# Sheet_byLIN.net
KiCad netlist of a schematic drawn in Altium Designer
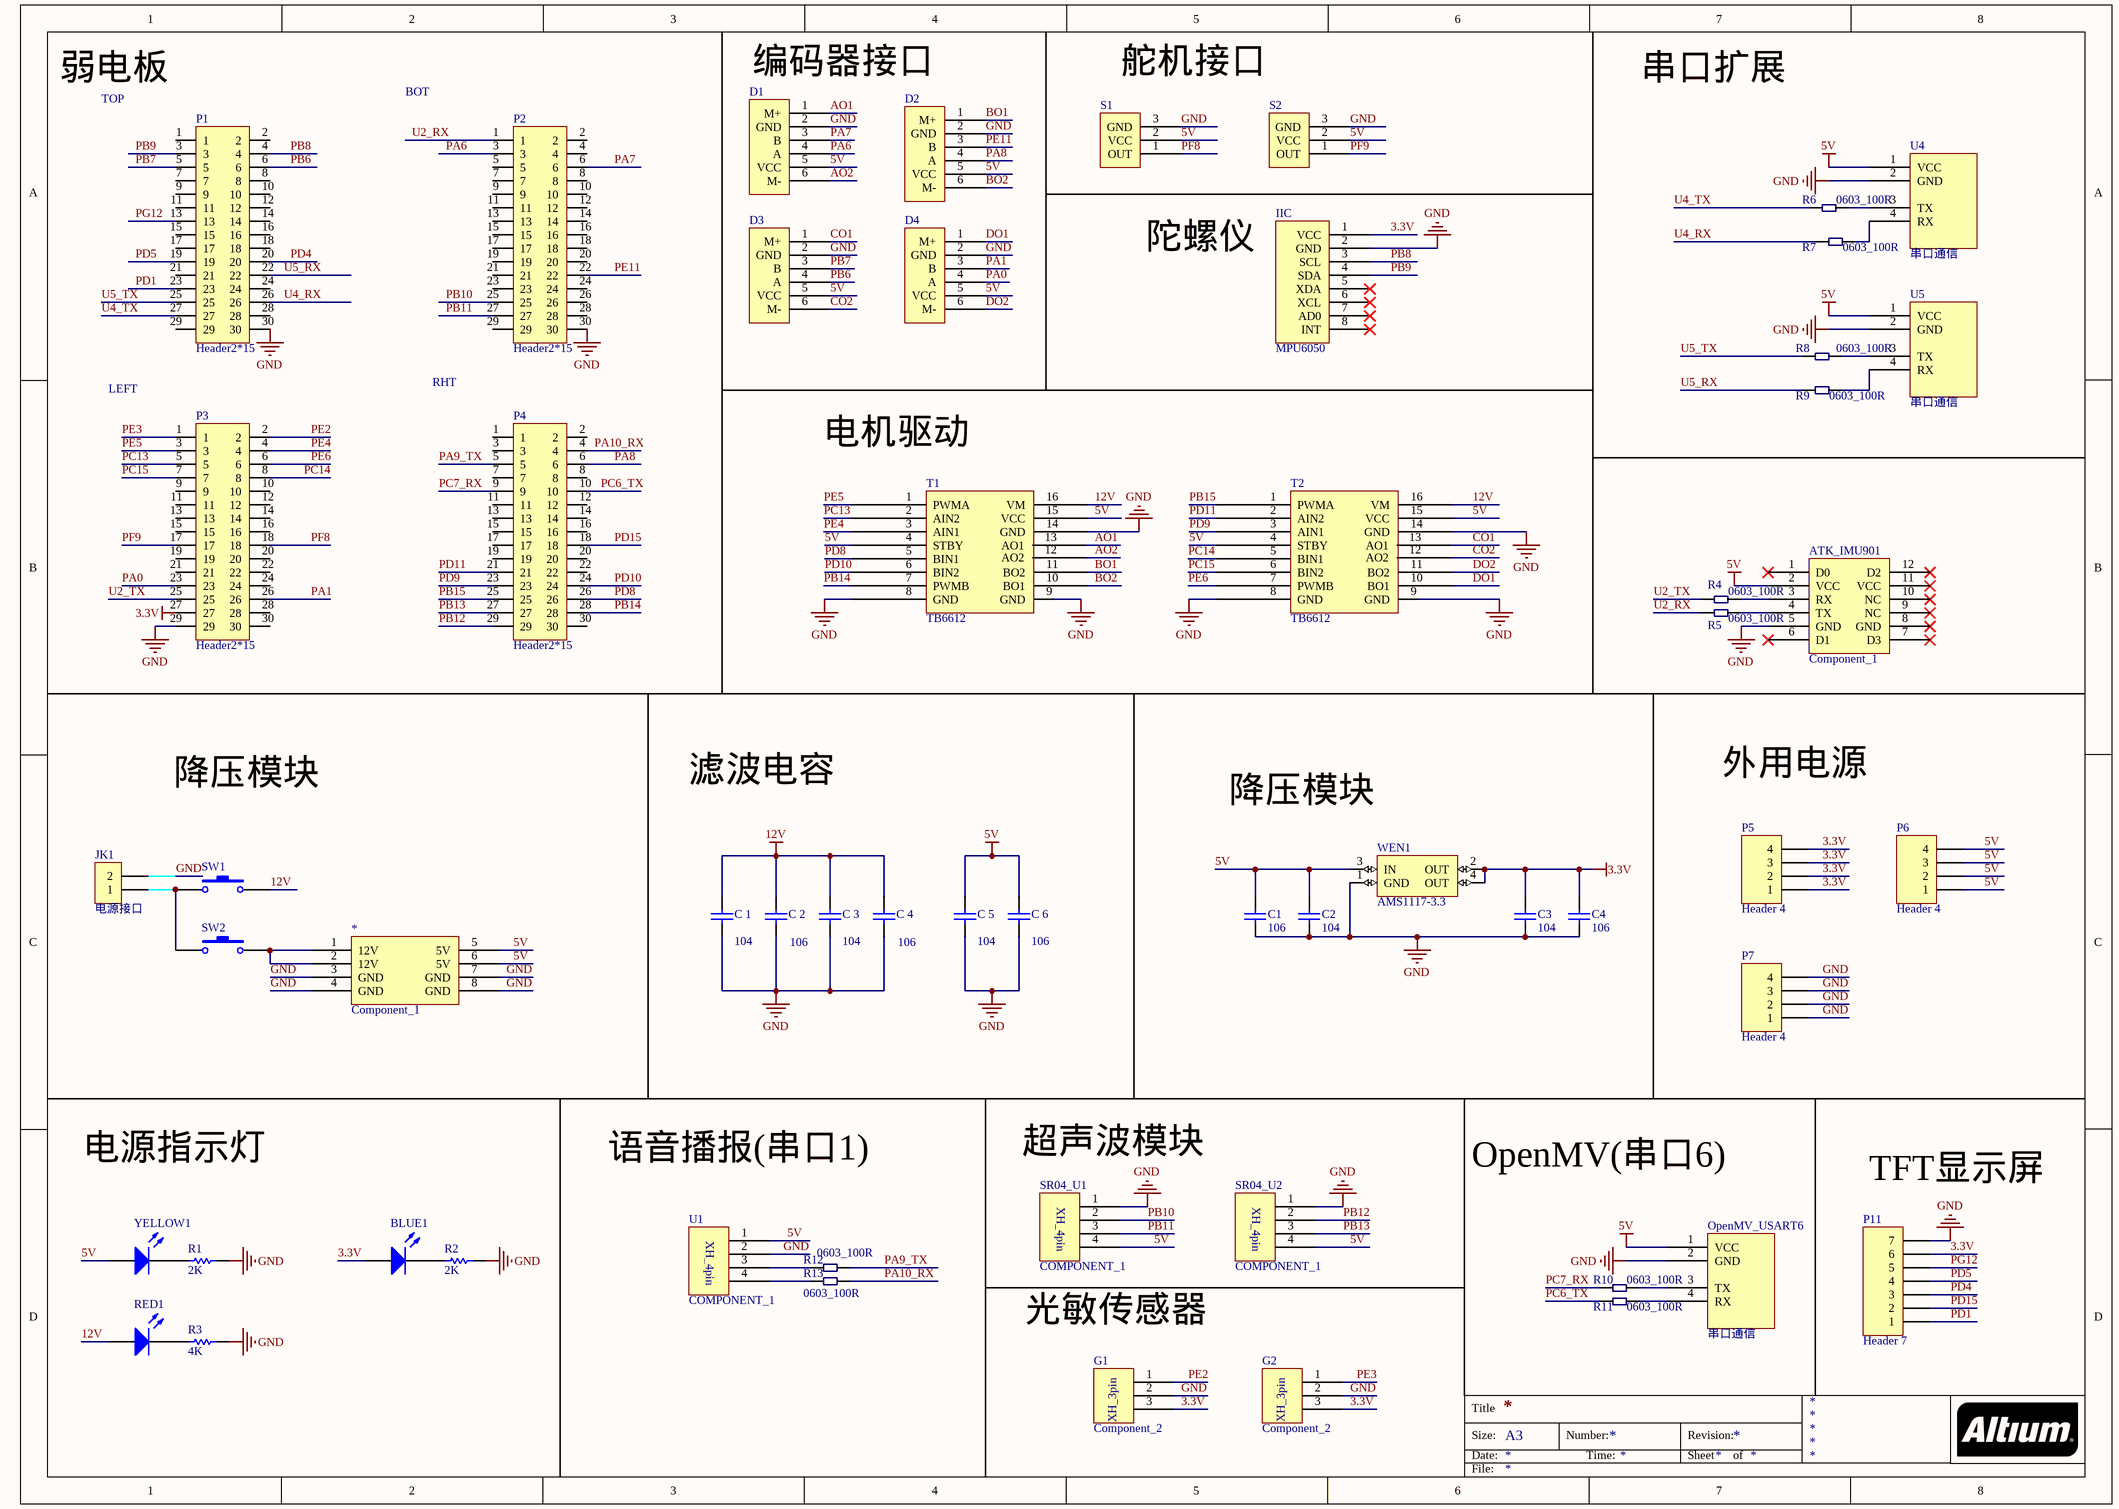
[diagram p0: Sheet_byLIN.SchDoc]

(export (version "E")
  (design (tool "Eeschema 10.0.6"))
  (components
    (comp (ref "*")
      (value "Component_1")
      (footprint "12-5V电源模块")
      (libsource (lib "稳压模块") (part "Component_1"))
    )
    (comp (ref "ATK_IMU901")
      (value "Component_1")
      (footprint "PCBComponent_1 - duplicate")
      (libsource (lib "MPU6050_v2") (part "Component_1"))
    )
    (comp (ref "BLUE1")
      (value "~")
      (footprint "LED 0805G")
      (description "Typical RED GaAs LED")
      (fields (field (name "PUBLISHER") "Altium Limited"))
      (libsource (lib "Miscellaneous Devices") (part "LED1"))
    )
    (comp (ref "C 1")
      (value "104")
      (footprint "C0805")
      (description "Capacitor")
      (fields (field (name "Comment") "Cap") (field (name "PUBLISHER") "Altium Limited"))
      (libsource (lib "Miscellaneous Devices") (part "Cap"))
    )
    (comp (ref "C 2")
      (value "106")
      (footprint "C0805")
      (description "Capacitor")
      (fields (field (name "Comment") "Cap") (field (name "PUBLISHER") "Altium Limited"))
      (libsource (lib "Miscellaneous Devices") (part "Cap"))
    )
    (comp (ref "C 3")
      (value "104")
      (footprint "C0805")
      (description "Capacitor")
      (fields (field (name "Comment") "Cap") (field (name "PUBLISHER") "Altium Limited"))
      (libsource (lib "Miscellaneous Devices") (part "Cap"))
    )
    (comp (ref "C 4")
      (value "106")
      (footprint "C0805")
      (description "Capacitor")
      (fields (field (name "Comment") "Cap") (field (name "PUBLISHER") "Altium Limited"))
      (libsource (lib "Miscellaneous Devices") (part "Cap"))
    )
    (comp (ref "C 5")
      (value "104")
      (footprint "C0805")
      (description "Capacitor")
      (fields (field (name "Comment") "Cap") (field (name "PUBLISHER") "Altium Limited"))
      (libsource (lib "Miscellaneous Devices") (part "Cap"))
    )
    (comp (ref "C 6")
      (value "106")
      (footprint "C0805")
      (description "Capacitor")
      (fields (field (name "Comment") "Cap") (field (name "PUBLISHER") "Altium Limited"))
      (libsource (lib "Miscellaneous Devices") (part "Cap"))
    )
    (comp (ref "C1")
      (value "106")
      (footprint "C 0603")
      (description "Capacitor")
      (fields (field (name "PUBLISHER") "Altium Limited"))
      (libsource (lib "Miscellaneous Devices") (part "Cap"))
    )
    (comp (ref "C2")
      (value "104")
      (footprint "C 0603")
      (description "Capacitor")
      (fields (field (name "PUBLISHER") "Altium Limited"))
      (libsource (lib "Miscellaneous Devices") (part "Cap"))
    )
    (comp (ref "C3")
      (value "104")
      (footprint "C 0603")
      (description "Capacitor")
      (fields (field (name "PUBLISHER") "Altium Limited"))
      (libsource (lib "Miscellaneous Devices") (part "Cap"))
    )
    (comp (ref "C4")
      (value "106")
      (footprint "C 0603")
      (description "Capacitor")
      (fields (field (name "PUBLISHER") "Altium Limited"))
      (libsource (lib "Miscellaneous Devices") (part "Cap"))
    )
    (comp (ref "D1") (value "~") (footprint "XH2.54-WI-6P") (libsource (lib "PCB_Project1") (part "P1")))
    (comp (ref "D2") (value "~") (footprint "XH2.54-WI-6P") (libsource (lib "PCB_Project1") (part "P1")))
    (comp (ref "D3") (value "~") (footprint "XH2.54-WI-6P") (libsource (lib "PCB_Project1") (part "P1")))
    (comp (ref "D4") (value "~") (footprint "XH2.54-WI-6P") (libsource (lib "PCB_Project1") (part "P1")))
    (comp (ref "G1")
      (value "Component_2")
      (footprint "XH2.54-LI-3P")
      (libsource (lib "XH_4PIN") (part "Component_2"))
    )
    (comp (ref "G2")
      (value "Component_2")
      (footprint "XH2.54-LI-3P")
      (libsource (lib "XH_4PIN") (part "Component_2"))
    )
    (comp (ref "IIC")
      (value "MPU6050")
      (footprint "HDR2.54-M-LI-8P")
      (libsource (lib "MPU6050") (part "MPU6050"))
    )
    (comp (ref "JK1") (value "电源接口") (footprint "XT-60") (libsource (lib "试验板") (part "VH2")))
    (comp (ref "OpenMV_USART6")
      (value "串口通信")
      (footprint "J-XH-4AW短")
      (libsource (lib "羽毛球团队") (part "XH2.54插座-4P"))
    )
    (comp (ref "P1")
      (value "Header2*15")
      (footprint "HDR2X15")
      (libsource (lib "主控V2.0核心板") (part "Header2*15"))
    )
    (comp (ref "P2")
      (value "Header2*15")
      (footprint "HDR2X15")
      (libsource (lib "主控V2.0核心板") (part "Header2*15"))
    )
    (comp (ref "P3")
      (value "Header2*15")
      (footprint "HDR2X15")
      (libsource (lib "主控V2.0核心板") (part "Header2*15"))
    )
    (comp (ref "P4")
      (value "Header2*15")
      (footprint "HDR2X15")
      (libsource (lib "主控V2.0核心板") (part "Header2*15"))
    )
    (comp (ref "P5")
      (value "Header 4")
      (footprint "HDR1X4")
      (description "Header, 4-Pin")
      (fields (field (name "PUBLISHER") "Altium Limited"))
      (libsource (lib "Miscellaneous Connectors") (part "Header 4"))
    )
    (comp (ref "P6")
      (value "Header 4")
      (footprint "HDR1X4")
      (description "Header, 4-Pin")
      (fields (field (name "PUBLISHER") "Altium Limited"))
      (libsource (lib "Miscellaneous Connectors") (part "Header 4"))
    )
    (comp (ref "P7")
      (value "Header 4")
      (footprint "HDR1X4")
      (description "Header, 4-Pin")
      (fields (field (name "PUBLISHER") "Altium Limited"))
      (libsource (lib "Miscellaneous Connectors") (part "Header 4"))
    )
    (comp (ref "P11")
      (value "Header 7")
      (footprint "HDR1X7")
      (description "Header, 7-Pin")
      (fields (field (name "PUBLISHER") "Altium Limited"))
      (libsource (lib "Miscellaneous Connectors") (part "Header 7"))
    )
    (comp (ref "R1")
      (value "2K")
      (footprint "R 0603")
      (description "Resistor")
      (fields (field (name "PUBLISHER") "Altium Limited"))
      (libsource (lib "Miscellaneous Devices") (part "Res1"))
    )
    (comp (ref "R2")
      (value "2K")
      (footprint "R 0603")
      (description "Resistor")
      (fields (field (name "PUBLISHER") "Altium Limited"))
      (libsource (lib "Miscellaneous Devices") (part "Res1"))
    )
    (comp (ref "R3")
      (value "4K")
      (footprint "R 0603")
      (description "Resistor")
      (fields (field (name "PUBLISHER") "Altium Limited"))
      (libsource (lib "Miscellaneous Devices") (part "Res1"))
    )
    (comp (ref "R4") (value "0603_100R") (footprint "0603_R") (libsource (lib "Schlib1") (part "RES")))
    (comp (ref "R5") (value "0603_100R") (footprint "0603_R") (libsource (lib "Schlib1") (part "RES")))
    (comp (ref "R6") (value "0603_100R") (footprint "0603_R") (libsource (lib "Schlib1") (part "RES")))
    (comp (ref "R7") (value "0603_100R") (footprint "0603_R") (libsource (lib "Schlib1") (part "RES")))
    (comp (ref "R8") (value "0603_100R") (footprint "0603_R") (libsource (lib "Schlib1") (part "RES")))
    (comp (ref "R9") (value "0603_100R") (footprint "0603_R") (libsource (lib "Schlib1") (part "RES")))
    (comp (ref "R10") (value "0603_100R") (footprint "0603_R") (libsource (lib "Schlib1") (part "RES")))
    (comp (ref "R11") (value "0603_100R") (footprint "0603_R") (libsource (lib "Schlib1") (part "RES")))
    (comp (ref "R12") (value "0603_100R") (footprint "0603_R") (libsource (lib "Schlib1") (part "RES")))
    (comp (ref "R13") (value "0603_100R") (footprint "0603_R") (libsource (lib "Schlib1") (part "RES")))
    (comp (ref "RED1")
      (value "~")
      (footprint "LED 0805G")
      (description "Typical RED GaAs LED")
      (fields (field (name "PUBLISHER") "Altium Limited"))
      (libsource (lib "Miscellaneous Devices") (part "LED1"))
    )
    (comp (ref "S1") (value "~") (footprint "HDR2.54-LI-3P") (libsource (lib "PCB_Project1") (part "sensor")))
    (comp (ref "S2") (value "~") (footprint "HDR2.54-LI-3P") (libsource (lib "PCB_Project1") (part "sensor")))
    (comp (ref "SR04_U1")
      (value "COMPONENT_1")
      (footprint "XH2.54-LI-4P")
      (libsource (lib "XH_4PIN") (part "COMPONENT_1"))
    )
    (comp (ref "SR04_U2")
      (value "COMPONENT_1")
      (footprint "XH2.54-LI-4P")
      (libsource (lib "XH_4PIN") (part "COMPONENT_1"))
    )
    (comp (ref "SW1")
      (value "~")
      (footprint "10*15mm船型开关")
      (description "Switch")
      (fields (field (name "PUBLISHER") "Altium Limited"))
      (libsource (lib "Miscellaneous Devices") (part "SW-PB"))
    )
    (comp (ref "SW2")
      (value "~")
      (footprint "10*15mm船型开关")
      (description "Switch")
      (fields (field (name "PUBLISHER") "Altium Limited"))
      (libsource (lib "Miscellaneous Devices") (part "SW-PB"))
    )
    (comp (ref "T1") (value "TB6612") (footprint "tb6612fng") (libsource (lib "自用") (part "Component_1_2")))
    (comp (ref "T2") (value "TB6612") (footprint "tb6612fng") (libsource (lib "自用") (part "Component_1_2")))
    (comp (ref "U1")
      (value "COMPONENT_1")
      (footprint "J-XH-4AW短")
      (libsource (lib "XH_4PIN") (part "COMPONENT_1"))
    )
    (comp (ref "U4") (value "串口通信") (footprint "J-XH-4AW短") (libsource (lib "羽毛球团队") (part "XH2.54插座-4P")))
    (comp (ref "U5") (value "串口通信") (footprint "J-XH-4AW短") (libsource (lib "羽毛球团队") (part "XH2.54插座-4P")))
    (comp (ref "WEN1")
      (value "AMS1117-3.3")
      (footprint "SOT-223")
      (libsource (lib "自用") (part "ASM1117-3.3"))
    )
    (comp (ref "YELLOW1")
      (value "~")
      (footprint "LED 0805G")
      (description "Typical RED GaAs LED")
      (fields (field (name "PUBLISHER") "Altium Limited"))
      (libsource (lib "Miscellaneous Devices") (part "LED1"))
    )
  )
  (nets
    (net (code "1") (name "/AO1") (class "Default")
      (node (ref "D1") (pin "1") (pinfunction "M+_1") (pintype "passive"))
      (node (ref "T1") (pin "13") (pinfunction "AO1_13") (pintype "passive"))
    )
    (net (code "2") (name "/AO2") (class "Default")
      (node (ref "D1") (pin "6") (pinfunction "M-_6") (pintype "passive"))
      (node (ref "T1") (pin "12") (pinfunction "AO2_12") (pintype "passive"))
    )
    (net (code "3") (name "/BO1") (class "Default")
      (node (ref "D2") (pin "1") (pinfunction "M+_1") (pintype "passive"))
      (node (ref "T1") (pin "11") (pinfunction "BO2_11") (pintype "passive"))
    )
    (net (code "4") (name "/BO2") (class "Default")
      (node (ref "D2") (pin "6") (pinfunction "M-_6") (pintype "passive"))
      (node (ref "T1") (pin "10") (pinfunction "BO1_10") (pintype "passive"))
    )
    (net (code "5") (name "/CO1") (class "Default")
      (node (ref "D3") (pin "1") (pinfunction "M+_1") (pintype "passive"))
      (node (ref "T2") (pin "13") (pinfunction "AO1_13") (pintype "passive"))
    )
    (net (code "6") (name "/CO2") (class "Default")
      (node (ref "D3") (pin "6") (pinfunction "M-_6") (pintype "passive"))
      (node (ref "T2") (pin "12") (pinfunction "AO2_12") (pintype "passive"))
    )
    (net (code "7") (name "/DO1") (class "Default")
      (node (ref "D4") (pin "1") (pinfunction "M+_1") (pintype "passive"))
      (node (ref "T2") (pin "10") (pinfunction "BO1_10") (pintype "passive"))
    )
    (net (code "8") (name "/DO2") (class "Default")
      (node (ref "D4") (pin "6") (pinfunction "M-_6") (pintype "passive"))
      (node (ref "T2") (pin "11") (pinfunction "BO2_11") (pintype "passive"))
    )
    (net (code "9") (name "/PA0") (class "Default")
      (node (ref "D4") (pin "4") (pinfunction "A_4") (pintype "passive"))
      (node (ref "P3") (pin "23") (pinfunction "23_23") (pintype "passive"))
    )
    (net (code "10") (name "/PA1") (class "Default")
      (node (ref "D4") (pin "3") (pinfunction "B_3") (pintype "passive"))
      (node (ref "P3") (pin "26") (pinfunction "26_26") (pintype "passive"))
    )
    (net (code "11") (name "/PA6") (class "Default")
      (node (ref "D1") (pin "4") (pinfunction "A_4") (pintype "passive"))
      (node (ref "P2") (pin "3") (pinfunction "3_3") (pintype "passive"))
    )
    (net (code "12") (name "/PA7") (class "Default")
      (node (ref "D1") (pin "3") (pinfunction "B_3") (pintype "passive"))
      (node (ref "P2") (pin "6") (pinfunction "6_6") (pintype "passive"))
    )
    (net (code "13") (name "/PA8") (class "Default")
      (node (ref "D2") (pin "4") (pinfunction "A_4") (pintype "passive"))
      (node (ref "P4") (pin "6") (pinfunction "6_6") (pintype "passive"))
    )
    (net (code "14") (name "/PA9_TX") (class "Default")
      (node (ref "P4") (pin "5") (pinfunction "5_5") (pintype "passive"))
      (node (ref "R12") (pin "2") (pinfunction "2_2") (pintype "passive"))
    )
    (net (code "15") (name "/PA10_RX") (class "Default")
      (node (ref "P4") (pin "4") (pinfunction "4_4") (pintype "passive"))
      (node (ref "R13") (pin "2") (pinfunction "2_2") (pintype "passive"))
    )
    (net (code "16") (name "/PB6") (class "Default")
      (node (ref "D3") (pin "4") (pinfunction "A_4") (pintype "passive"))
      (node (ref "P1") (pin "6") (pinfunction "6_6") (pintype "passive"))
    )
    (net (code "17") (name "/PB7") (class "Default")
      (node (ref "D3") (pin "3") (pinfunction "B_3") (pintype "passive"))
      (node (ref "P1") (pin "5") (pinfunction "5_5") (pintype "passive"))
    )
    (net (code "18") (name "/PB8") (class "Default")
      (node (ref "IIC") (pin "3") (pinfunction "SCL_3") (pintype "passive"))
      (node (ref "P1") (pin "4") (pinfunction "4_4") (pintype "passive"))
    )
    (net (code "19") (name "/PB9") (class "Default")
      (node (ref "IIC") (pin "4") (pinfunction "SDA_4") (pintype "passive"))
      (node (ref "P1") (pin "3") (pinfunction "3_3") (pintype "passive"))
    )
    (net (code "20") (name "/PB10") (class "Default")
      (node (ref "P2") (pin "25") (pinfunction "25_25") (pintype "passive"))
      (node (ref "SR04_U1") (pin "2") (pinfunction "2_2") (pintype "passive"))
    )
    (net (code "21") (name "/PB11") (class "Default")
      (node (ref "P2") (pin "27") (pinfunction "27_27") (pintype "passive"))
      (node (ref "SR04_U1") (pin "3") (pinfunction "3_3") (pintype "passive"))
    )
    (net (code "22") (name "/PB12") (class "Default")
      (node (ref "P4") (pin "29") (pinfunction "29_29") (pintype "passive"))
      (node (ref "SR04_U2") (pin "2") (pinfunction "2_2") (pintype "passive"))
    )
    (net (code "23") (name "/PB13") (class "Default")
      (node (ref "P4") (pin "27") (pinfunction "27_27") (pintype "passive"))
      (node (ref "SR04_U2") (pin "3") (pinfunction "3_3") (pintype "passive"))
    )
    (net (code "24") (name "/PB14") (class "Default")
      (node (ref "P4") (pin "28") (pinfunction "28_28") (pintype "passive"))
      (node (ref "T1") (pin "7") (pinfunction "PWMB_7") (pintype "passive"))
    )
    (net (code "25") (name "/PB15") (class "Default")
      (node (ref "P4") (pin "25") (pinfunction "25_25") (pintype "passive"))
      (node (ref "T2") (pin "1") (pinfunction "PWMA_1") (pintype "passive"))
    )
    (net (code "26") (name "/PC6_TX") (class "Default")
      (node (ref "P4") (pin "10") (pinfunction "10_10") (pintype "passive"))
      (node (ref "R11") (pin "1") (pinfunction "1_1") (pintype "passive"))
    )
    (net (code "27") (name "/PC7_RX") (class "Default")
      (node (ref "P4") (pin "9") (pinfunction "9_9") (pintype "passive"))
      (node (ref "R10") (pin "1") (pinfunction "1_1") (pintype "passive"))
    )
    (net (code "28") (name "/PC13") (class "Default")
      (node (ref "P3") (pin "5") (pinfunction "5_5") (pintype "passive"))
      (node (ref "T1") (pin "2") (pinfunction "AIN2_2") (pintype "passive"))
    )
    (net (code "29") (name "/PC14") (class "Default")
      (node (ref "P3") (pin "8") (pinfunction "8_8") (pintype "passive"))
      (node (ref "T2") (pin "5") (pinfunction "BIN1_5") (pintype "passive"))
    )
    (net (code "30") (name "/PC15") (class "Default")
      (node (ref "P3") (pin "7") (pinfunction "7_7") (pintype "passive"))
      (node (ref "T2") (pin "6") (pinfunction "BIN2_6") (pintype "passive"))
    )
    (net (code "31") (name "/PD1") (class "Default")
      (node (ref "P1") (pin "23") (pinfunction "23_23") (pintype "passive"))
      (node (ref "P11") (pin "1") (pinfunction "1_1") (pintype "passive"))
    )
    (net (code "32") (name "/PD4") (class "Default")
      (node (ref "P1") (pin "20") (pinfunction "20_20") (pintype "passive"))
      (node (ref "P11") (pin "3") (pinfunction "3_3") (pintype "passive"))
    )
    (net (code "33") (name "/PD5") (class "Default")
      (node (ref "P1") (pin "19") (pinfunction "19_19") (pintype "passive"))
      (node (ref "P11") (pin "4") (pinfunction "4_4") (pintype "passive"))
    )
    (net (code "34") (name "/PD8") (class "Default")
      (node (ref "P4") (pin "26") (pinfunction "26_26") (pintype "passive"))
      (node (ref "T1") (pin "5") (pinfunction "BIN1_5") (pintype "passive"))
    )
    (net (code "35") (name "/PD9") (class "Default")
      (node (ref "P4") (pin "23") (pinfunction "23_23") (pintype "passive"))
      (node (ref "T2") (pin "3") (pinfunction "AIN1_3") (pintype "passive"))
    )
    (net (code "36") (name "/PD10") (class "Default")
      (node (ref "P4") (pin "24") (pinfunction "24_24") (pintype "passive"))
      (node (ref "T1") (pin "6") (pinfunction "BIN2_6") (pintype "passive"))
    )
    (net (code "37") (name "/PD11") (class "Default")
      (node (ref "P4") (pin "21") (pinfunction "21_21") (pintype "passive"))
      (node (ref "T2") (pin "2") (pinfunction "AIN2_2") (pintype "passive"))
    )
    (net (code "38") (name "/PD15") (class "Default")
      (node (ref "P11") (pin "2") (pinfunction "2_2") (pintype "passive"))
      (node (ref "P4") (pin "18") (pinfunction "18_18") (pintype "passive"))
    )
    (net (code "39") (name "/PE2") (class "Default")
      (node (ref "G1") (pin "1") (pinfunction "1_1") (pintype "passive"))
      (node (ref "P3") (pin "2") (pinfunction "2_2") (pintype "passive"))
    )
    (net (code "40") (name "/PE3") (class "Default")
      (node (ref "G2") (pin "1") (pinfunction "1_1") (pintype "passive"))
      (node (ref "P3") (pin "1") (pinfunction "1_1") (pintype "passive"))
    )
    (net (code "41") (name "/PE4") (class "Default")
      (node (ref "P3") (pin "4") (pinfunction "4_4") (pintype "passive"))
      (node (ref "T1") (pin "3") (pinfunction "AIN1_3") (pintype "passive"))
    )
    (net (code "42") (name "/PE5") (class "Default")
      (node (ref "P3") (pin "3") (pinfunction "3_3") (pintype "passive"))
      (node (ref "T1") (pin "1") (pinfunction "PWMA_1") (pintype "passive"))
    )
    (net (code "43") (name "/PE6") (class "Default")
      (node (ref "P3") (pin "6") (pinfunction "6_6") (pintype "passive"))
      (node (ref "T2") (pin "7") (pinfunction "PWMB_7") (pintype "passive"))
    )
    (net (code "44") (name "/PE11") (class "Default")
      (node (ref "D2") (pin "3") (pinfunction "B_3") (pintype "passive"))
      (node (ref "P2") (pin "22") (pinfunction "22_22") (pintype "passive"))
    )
    (net (code "45") (name "/PF8") (class "Default")
      (node (ref "P3") (pin "18") (pinfunction "18_18") (pintype "passive"))
      (node (ref "S1") (pin "1") (pinfunction "OUT_1") (pintype "passive"))
    )
    (net (code "46") (name "/PF9") (class "Default")
      (node (ref "P3") (pin "17") (pinfunction "17_17") (pintype "passive"))
      (node (ref "S2") (pin "1") (pinfunction "OUT_1") (pintype "passive"))
    )
    (net (code "47") (name "/PG12") (class "Default")
      (node (ref "P1") (pin "13") (pinfunction "13_13") (pintype "passive"))
      (node (ref "P11") (pin "5") (pinfunction "5_5") (pintype "passive"))
    )
    (net (code "48") (name "/U2_RX") (class "Default")
      (node (ref "P2") (pin "1") (pinfunction "1_1") (pintype "passive"))
      (node (ref "R5") (pin "1") (pinfunction "1_1") (pintype "passive"))
    )
    (net (code "49") (name "/U2_TX") (class "Default")
      (node (ref "P3") (pin "25") (pinfunction "25_25") (pintype "passive"))
      (node (ref "R4") (pin "1") (pinfunction "1_1") (pintype "passive"))
    )
    (net (code "50") (name "/U4_RX") (class "Default")
      (node (ref "P1") (pin "26") (pinfunction "26_26") (pintype "passive"))
      (node (ref "R7") (pin "1") (pinfunction "1_1") (pintype "passive"))
    )
    (net (code "51") (name "/U4_TX") (class "Default")
      (node (ref "P1") (pin "27") (pinfunction "27_27") (pintype "passive"))
      (node (ref "R6") (pin "1") (pinfunction "1_1") (pintype "passive"))
    )
    (net (code "52") (name "/U5_RX") (class "Default")
      (node (ref "P1") (pin "22") (pinfunction "22_22") (pintype "passive"))
      (node (ref "R9") (pin "1") (pinfunction "1_1") (pintype "passive"))
    )
    (net (code "53") (name "/U5_TX") (class "Default")
      (node (ref "P1") (pin "25") (pinfunction "25_25") (pintype "passive"))
      (node (ref "R8") (pin "1") (pinfunction "1_1") (pintype "passive"))
    )
    (net (code "54") (name "3.3V") (class "Default")
      (node (ref "BLUE1") (pin "1") (pinfunction "A_1") (pintype "passive"))
      (node (ref "C3") (pin "2") (pinfunction "2_2") (pintype "passive"))
      (node (ref "C4") (pin "2") (pinfunction "2_2") (pintype "passive"))
      (node (ref "G1") (pin "3") (pinfunction "3_3") (pintype "passive"))
      (node (ref "G2") (pin "3") (pinfunction "3_3") (pintype "passive"))
      (node (ref "IIC") (pin "1") (pinfunction "VCC_1") (pintype "passive"))
      (node (ref "P11") (pin "6") (pinfunction "6_6") (pintype "passive"))
      (node (ref "P3") (pin "27") (pinfunction "27_27") (pintype "passive"))
      (node (ref "P5") (pin "1") (pinfunction "1_1") (pintype "passive"))
      (node (ref "P5") (pin "2") (pinfunction "2_2") (pintype "passive"))
      (node (ref "P5") (pin "3") (pinfunction "3_3") (pintype "passive"))
      (node (ref "P5") (pin "4") (pinfunction "4_4") (pintype "passive"))
      (node (ref "WEN1") (pin "2") (pinfunction "OUT_2") (pintype "bidirectional"))
      (node (ref "WEN1") (pin "4") (pinfunction "OUT_4") (pintype "bidirectional"))
    )
    (net (code "55") (name "5V") (class "Default")
      (node (ref "*") (pin "5") (pinfunction "5V_5") (pintype "passive"))
      (node (ref "*") (pin "6") (pinfunction "5V_6") (pintype "passive"))
      (node (ref "ATK_IMU901") (pin "2") (pinfunction "VCC_2") (pintype "passive"))
      (node (ref "C 5") (pin "2") (pinfunction "2_2") (pintype "passive"))
      (node (ref "C 6") (pin "2") (pinfunction "2_2") (pintype "passive"))
      (node (ref "C1") (pin "2") (pinfunction "2_2") (pintype "passive"))
      (node (ref "C2") (pin "2") (pinfunction "2_2") (pintype "passive"))
      (node (ref "D1") (pin "5") (pinfunction "VCC_5") (pintype "passive"))
      (node (ref "D2") (pin "5") (pinfunction "VCC_5") (pintype "passive"))
      (node (ref "D3") (pin "5") (pinfunction "VCC_5") (pintype "passive"))
      (node (ref "D4") (pin "5") (pinfunction "VCC_5") (pintype "passive"))
      (node (ref "OpenMV_USART6") (pin "1") (pinfunction "VCC_1") (pintype "passive"))
      (node (ref "P6") (pin "1") (pinfunction "1_1") (pintype "passive"))
      (node (ref "P6") (pin "2") (pinfunction "2_2") (pintype "passive"))
      (node (ref "P6") (pin "3") (pinfunction "3_3") (pintype "passive"))
      (node (ref "P6") (pin "4") (pinfunction "4_4") (pintype "passive"))
      (node (ref "S1") (pin "2") (pinfunction "VCC_2") (pintype "passive"))
      (node (ref "S2") (pin "2") (pinfunction "VCC_2") (pintype "passive"))
      (node (ref "SR04_U1") (pin "4") (pinfunction "4_4") (pintype "passive"))
      (node (ref "SR04_U2") (pin "4") (pinfunction "4_4") (pintype "passive"))
      (node (ref "T1") (pin "15") (pinfunction "VCC_15") (pintype "passive"))
      (node (ref "T1") (pin "4") (pinfunction "STBY_4") (pintype "passive"))
      (node (ref "T2") (pin "15") (pinfunction "VCC_15") (pintype "passive"))
      (node (ref "T2") (pin "4") (pinfunction "STBY_4") (pintype "passive"))
      (node (ref "U1") (pin "1") (pinfunction "1_1") (pintype "passive"))
      (node (ref "U4") (pin "1") (pinfunction "VCC_1") (pintype "passive"))
      (node (ref "U5") (pin "1") (pinfunction "VCC_1") (pintype "passive"))
      (node (ref "WEN1") (pin "3") (pinfunction "IN_3") (pintype "bidirectional"))
      (node (ref "YELLOW1") (pin "1") (pinfunction "A_1") (pintype "passive"))
    )
    (net (code "56") (name "12V") (class "Default")
      (node (ref "C 1") (pin "2") (pinfunction "2_2") (pintype "passive"))
      (node (ref "C 2") (pin "2") (pinfunction "2_2") (pintype "passive"))
      (node (ref "C 3") (pin "2") (pinfunction "2_2") (pintype "passive"))
      (node (ref "C 4") (pin "2") (pinfunction "2_2") (pintype "passive"))
      (node (ref "RED1") (pin "1") (pinfunction "A_1") (pintype "passive"))
      (node (ref "SW1") (pin "2") (pinfunction "2_2") (pintype "passive"))
      (node (ref "T1") (pin "16") (pinfunction "VM_16") (pintype "passive"))
      (node (ref "T2") (pin "16") (pinfunction "VM_16") (pintype "passive"))
    )
    (net (code "57") (name "GND") (class "Default")
      (node (ref "*") (pin "3") (pinfunction "GND_3") (pintype "passive"))
      (node (ref "*") (pin "4") (pinfunction "GND_4") (pintype "passive"))
      (node (ref "*") (pin "7") (pinfunction "GND_7") (pintype "passive"))
      (node (ref "*") (pin "8") (pinfunction "GND_8") (pintype "passive"))
      (node (ref "ATK_IMU901") (pin "5") (pinfunction "GND_5") (pintype "passive"))
      (node (ref "C 1") (pin "1") (pinfunction "1_1") (pintype "passive"))
      (node (ref "C 2") (pin "1") (pinfunction "1_1") (pintype "passive"))
      (node (ref "C 3") (pin "1") (pinfunction "1_1") (pintype "passive"))
      (node (ref "C 4") (pin "1") (pinfunction "1_1") (pintype "passive"))
      (node (ref "C 5") (pin "1") (pinfunction "1_1") (pintype "passive"))
      (node (ref "C 6") (pin "1") (pinfunction "1_1") (pintype "passive"))
      (node (ref "C1") (pin "1") (pinfunction "1_1") (pintype "passive"))
      (node (ref "C2") (pin "1") (pinfunction "1_1") (pintype "passive"))
      (node (ref "C3") (pin "1") (pinfunction "1_1") (pintype "passive"))
      (node (ref "C4") (pin "1") (pinfunction "1_1") (pintype "passive"))
      (node (ref "D1") (pin "2") (pinfunction "GND_2") (pintype "passive"))
      (node (ref "D2") (pin "2") (pinfunction "GND_2") (pintype "passive"))
      (node (ref "D3") (pin "2") (pinfunction "GND_2") (pintype "passive"))
      (node (ref "D4") (pin "2") (pinfunction "GND_2") (pintype "passive"))
      (node (ref "G1") (pin "2") (pinfunction "2_2") (pintype "passive"))
      (node (ref "G2") (pin "2") (pinfunction "2_2") (pintype "passive"))
      (node (ref "IIC") (pin "2") (pinfunction "GND_2") (pintype "passive"))
      (node (ref "JK1") (pin "2") (pinfunction "2_2") (pintype "passive"))
      (node (ref "OpenMV_USART6") (pin "2") (pinfunction "GND_2") (pintype "passive"))
      (node (ref "P1") (pin "30") (pinfunction "30_30") (pintype "passive"))
      (node (ref "P11") (pin "7") (pinfunction "7_7") (pintype "passive"))
      (node (ref "P2") (pin "30") (pinfunction "30_30") (pintype "passive"))
      (node (ref "P3") (pin "29") (pinfunction "29_29") (pintype "passive"))
      (node (ref "P7") (pin "1") (pinfunction "1_1") (pintype "passive"))
      (node (ref "P7") (pin "2") (pinfunction "2_2") (pintype "passive"))
      (node (ref "P7") (pin "3") (pinfunction "3_3") (pintype "passive"))
      (node (ref "P7") (pin "4") (pinfunction "4_4") (pintype "passive"))
      (node (ref "R1") (pin "2") (pinfunction "2_2") (pintype "passive"))
      (node (ref "R2") (pin "2") (pinfunction "2_2") (pintype "passive"))
      (node (ref "R3") (pin "2") (pinfunction "2_2") (pintype "passive"))
      (node (ref "S1") (pin "3") (pinfunction "GND_3") (pintype "passive"))
      (node (ref "S2") (pin "3") (pinfunction "GND_3") (pintype "passive"))
      (node (ref "SR04_U1") (pin "1") (pinfunction "1_1") (pintype "passive"))
      (node (ref "SR04_U2") (pin "1") (pinfunction "1_1") (pintype "passive"))
      (node (ref "T1") (pin "14") (pinfunction "GND_14") (pintype "passive"))
      (node (ref "T1") (pin "8") (pinfunction "GND_8") (pintype "passive"))
      (node (ref "T1") (pin "9") (pinfunction "GND_9") (pintype "passive"))
      (node (ref "T2") (pin "14") (pinfunction "GND_14") (pintype "passive"))
      (node (ref "T2") (pin "8") (pinfunction "GND_8") (pintype "passive"))
      (node (ref "T2") (pin "9") (pinfunction "GND_9") (pintype "passive"))
      (node (ref "U1") (pin "2") (pinfunction "2_2") (pintype "passive"))
      (node (ref "U4") (pin "2") (pinfunction "GND_2") (pintype "passive"))
      (node (ref "U5") (pin "2") (pinfunction "GND_2") (pintype "passive"))
      (node (ref "WEN1") (pin "1") (pinfunction "GND_1") (pintype "bidirectional"))
    )
    (net (code "58") (name "Net-(*-12V-Pad1)") (class "Default")
      (node (ref "*") (pin "1") (pinfunction "12V_1") (pintype "passive"))
      (node (ref "*") (pin "2") (pinfunction "12V_2") (pintype "passive"))
      (node (ref "SW2") (pin "2") (pinfunction "2_2") (pintype "passive"))
    )
    (net (code "59") (name "Net-(ATK_IMU901-RX)") (class "Default")
      (node (ref "ATK_IMU901") (pin "3") (pinfunction "RX_3") (pintype "passive"))
      (node (ref "R4") (pin "2") (pinfunction "2_2") (pintype "passive"))
    )
    (net (code "60") (name "Net-(ATK_IMU901-TX)") (class "Default")
      (node (ref "ATK_IMU901") (pin "4") (pinfunction "TX_4") (pintype "passive"))
      (node (ref "R5") (pin "2") (pinfunction "2_2") (pintype "passive"))
    )
    (net (code "61") (name "Net-(BLUE1-K)") (class "Default")
      (node (ref "BLUE1") (pin "2") (pinfunction "K_2") (pintype "passive"))
      (node (ref "R2") (pin "1") (pinfunction "1_1") (pintype "passive"))
    )
    (net (code "62") (name "Net-(JK1-Pad1)") (class "Default")
      (node (ref "JK1") (pin "1") (pinfunction "1_1") (pintype "passive"))
      (node (ref "SW1") (pin "1") (pinfunction "1_1") (pintype "passive"))
      (node (ref "SW2") (pin "1") (pinfunction "1_1") (pintype "passive"))
    )
    (net (code "63") (name "Net-(OpenMV_USART6-RX)") (class "Default")
      (node (ref "OpenMV_USART6") (pin "4") (pinfunction "RX_4") (pintype "passive"))
      (node (ref "R11") (pin "2") (pinfunction "2_2") (pintype "passive"))
    )
    (net (code "64") (name "Net-(OpenMV_USART6-TX)") (class "Default")
      (node (ref "OpenMV_USART6") (pin "3") (pinfunction "TX_3") (pintype "passive"))
      (node (ref "R10") (pin "2") (pinfunction "2_2") (pintype "passive"))
    )
    (net (code "65") (name "Net-(R12-Pad1)") (class "Default")
      (node (ref "R12") (pin "1") (pinfunction "1_1") (pintype "passive"))
      (node (ref "U1") (pin "3") (pinfunction "3_3") (pintype "passive"))
    )
    (net (code "66") (name "Net-(R13-Pad1)") (class "Default")
      (node (ref "R13") (pin "1") (pinfunction "1_1") (pintype "passive"))
      (node (ref "U1") (pin "4") (pinfunction "4_4") (pintype "passive"))
    )
    (net (code "67") (name "Net-(RED1-K)") (class "Default")
      (node (ref "R3") (pin "1") (pinfunction "1_1") (pintype "passive"))
      (node (ref "RED1") (pin "2") (pinfunction "K_2") (pintype "passive"))
    )
    (net (code "68") (name "Net-(U4-RX)") (class "Default")
      (node (ref "R7") (pin "2") (pinfunction "2_2") (pintype "passive"))
      (node (ref "U4") (pin "4") (pinfunction "RX_4") (pintype "passive"))
    )
    (net (code "69") (name "Net-(U4-TX)") (class "Default")
      (node (ref "R6") (pin "2") (pinfunction "2_2") (pintype "passive"))
      (node (ref "U4") (pin "3") (pinfunction "TX_3") (pintype "passive"))
    )
    (net (code "70") (name "Net-(U5-RX)") (class "Default")
      (node (ref "R9") (pin "2") (pinfunction "2_2") (pintype "passive"))
      (node (ref "U5") (pin "4") (pinfunction "RX_4") (pintype "passive"))
    )
    (net (code "71") (name "Net-(U5-TX)") (class "Default")
      (node (ref "R8") (pin "2") (pinfunction "2_2") (pintype "passive"))
      (node (ref "U5") (pin "3") (pinfunction "TX_3") (pintype "passive"))
    )
    (net (code "72") (name "Net-(YELLOW1-K)") (class "Default")
      (node (ref "R1") (pin "1") (pinfunction "1_1") (pintype "passive"))
      (node (ref "YELLOW1") (pin "2") (pinfunction "K_2") (pintype "passive"))
    )
    (net (code "73") (name "unconnected-(ATK_IMU901-D0-Pad1)") (class "Default")
      (node (ref "ATK_IMU901") (pin "1") (pinfunction "D0_1") (pintype "passive+no_connect"))
    )
    (net (code "74") (name "unconnected-(ATK_IMU901-D1-Pad6)") (class "Default")
      (node (ref "ATK_IMU901") (pin "6") (pinfunction "D1_6") (pintype "passive+no_connect"))
    )
    (net (code "75") (name "unconnected-(ATK_IMU901-D2-Pad12)") (class "Default")
      (node (ref "ATK_IMU901") (pin "12") (pinfunction "D2_12") (pintype "passive+no_connect"))
    )
    (net (code "76") (name "unconnected-(ATK_IMU901-D3-Pad7)") (class "Default")
      (node (ref "ATK_IMU901") (pin "7") (pinfunction "D3_7") (pintype "passive+no_connect"))
    )
    (net (code "77") (name "unconnected-(ATK_IMU901-GND-Pad8)") (class "Default")
      (node (ref "ATK_IMU901") (pin "8") (pinfunction "GND_8") (pintype "passive+no_connect"))
    )
    (net (code "78") (name "unconnected-(ATK_IMU901-NC-Pad9)") (class "Default")
      (node (ref "ATK_IMU901") (pin "9") (pinfunction "NC_9") (pintype "passive+no_connect"))
    )
    (net (code "79") (name "unconnected-(ATK_IMU901-NC-Pad10)") (class "Default")
      (node (ref "ATK_IMU901") (pin "10") (pinfunction "NC_10") (pintype "passive+no_connect"))
    )
    (net (code "80") (name "unconnected-(ATK_IMU901-VCC-Pad11)") (class "Default")
      (node (ref "ATK_IMU901") (pin "11") (pinfunction "VCC_11") (pintype "passive+no_connect"))
    )
    (net (code "81") (name "unconnected-(IIC-AD0-Pad7)") (class "Default")
      (node (ref "IIC") (pin "7") (pinfunction "AD0_7") (pintype "passive+no_connect"))
    )
    (net (code "82") (name "unconnected-(IIC-INT-Pad8)") (class "Default")
      (node (ref "IIC") (pin "8") (pinfunction "INT_8") (pintype "passive+no_connect"))
    )
    (net (code "83") (name "unconnected-(IIC-XCL-Pad6)") (class "Default")
      (node (ref "IIC") (pin "6") (pinfunction "XCL_6") (pintype "passive+no_connect"))
    )
    (net (code "84") (name "unconnected-(IIC-XDA-Pad5)") (class "Default")
      (node (ref "IIC") (pin "5") (pinfunction "XDA_5") (pintype "passive+no_connect"))
    )
    (net (code "85") (name "unconnected-(P1-Pad1)") (class "Default")
      (node (ref "P1") (pin "1") (pinfunction "1_1") (pintype "passive"))
    )
    (net (code "86") (name "unconnected-(P1-Pad2)") (class "Default")
      (node (ref "P1") (pin "2") (pinfunction "2_2") (pintype "passive"))
    )
    (net (code "87") (name "unconnected-(P1-Pad7)") (class "Default")
      (node (ref "P1") (pin "7") (pinfunction "7_7") (pintype "passive"))
    )
    (net (code "88") (name "unconnected-(P1-Pad8)") (class "Default")
      (node (ref "P1") (pin "8") (pinfunction "8_8") (pintype "passive"))
    )
    (net (code "89") (name "unconnected-(P1-Pad9)") (class "Default")
      (node (ref "P1") (pin "9") (pinfunction "9_9") (pintype "passive"))
    )
    (net (code "90") (name "unconnected-(P1-Pad10)") (class "Default")
      (node (ref "P1") (pin "10") (pinfunction "10_10") (pintype "passive"))
    )
    (net (code "91") (name "unconnected-(P1-Pad11)") (class "Default")
      (node (ref "P1") (pin "11") (pinfunction "11_11") (pintype "passive"))
    )
    (net (code "92") (name "unconnected-(P1-Pad12)") (class "Default")
      (node (ref "P1") (pin "12") (pinfunction "12_12") (pintype "passive"))
    )
    (net (code "93") (name "unconnected-(P1-Pad14)") (class "Default")
      (node (ref "P1") (pin "14") (pinfunction "14_14") (pintype "passive"))
    )
    (net (code "94") (name "unconnected-(P1-Pad15)") (class "Default")
      (node (ref "P1") (pin "15") (pinfunction "15_15") (pintype "passive"))
    )
    (net (code "95") (name "unconnected-(P1-Pad16)") (class "Default")
      (node (ref "P1") (pin "16") (pinfunction "16_16") (pintype "passive"))
    )
    (net (code "96") (name "unconnected-(P1-Pad17)") (class "Default")
      (node (ref "P1") (pin "17") (pinfunction "17_17") (pintype "passive"))
    )
    (net (code "97") (name "unconnected-(P1-Pad18)") (class "Default")
      (node (ref "P1") (pin "18") (pinfunction "18_18") (pintype "passive"))
    )
    (net (code "98") (name "unconnected-(P1-Pad21)") (class "Default")
      (node (ref "P1") (pin "21") (pinfunction "21_21") (pintype "passive"))
    )
    (net (code "99") (name "unconnected-(P1-Pad24)") (class "Default")
      (node (ref "P1") (pin "24") (pinfunction "24_24") (pintype "passive"))
    )
    (net (code "100") (name "unconnected-(P1-Pad28)") (class "Default")
      (node (ref "P1") (pin "28") (pinfunction "28_28") (pintype "passive"))
    )
    (net (code "101") (name "unconnected-(P1-Pad29)") (class "Default")
      (node (ref "P1") (pin "29") (pinfunction "29_29") (pintype "passive"))
    )
    (net (code "102") (name "unconnected-(P2-Pad2)") (class "Default")
      (node (ref "P2") (pin "2") (pinfunction "2_2") (pintype "passive"))
    )
    (net (code "103") (name "unconnected-(P2-Pad4)") (class "Default")
      (node (ref "P2") (pin "4") (pinfunction "4_4") (pintype "passive"))
    )
    (net (code "104") (name "unconnected-(P2-Pad5)") (class "Default")
      (node (ref "P2") (pin "5") (pinfunction "5_5") (pintype "passive"))
    )
    (net (code "105") (name "unconnected-(P2-Pad7)") (class "Default")
      (node (ref "P2") (pin "7") (pinfunction "7_7") (pintype "passive"))
    )
    (net (code "106") (name "unconnected-(P2-Pad8)") (class "Default")
      (node (ref "P2") (pin "8") (pinfunction "8_8") (pintype "passive"))
    )
    (net (code "107") (name "unconnected-(P2-Pad9)") (class "Default")
      (node (ref "P2") (pin "9") (pinfunction "9_9") (pintype "passive"))
    )
    (net (code "108") (name "unconnected-(P2-Pad10)") (class "Default")
      (node (ref "P2") (pin "10") (pinfunction "10_10") (pintype "passive"))
    )
    (net (code "109") (name "unconnected-(P2-Pad11)") (class "Default")
      (node (ref "P2") (pin "11") (pinfunction "11_11") (pintype "passive"))
    )
    (net (code "110") (name "unconnected-(P2-Pad12)") (class "Default")
      (node (ref "P2") (pin "12") (pinfunction "12_12") (pintype "passive"))
    )
    (net (code "111") (name "unconnected-(P2-Pad13)") (class "Default")
      (node (ref "P2") (pin "13") (pinfunction "13_13") (pintype "passive"))
    )
    (net (code "112") (name "unconnected-(P2-Pad14)") (class "Default")
      (node (ref "P2") (pin "14") (pinfunction "14_14") (pintype "passive"))
    )
    (net (code "113") (name "unconnected-(P2-Pad15)") (class "Default")
      (node (ref "P2") (pin "15") (pinfunction "15_15") (pintype "passive"))
    )
    (net (code "114") (name "unconnected-(P2-Pad16)") (class "Default")
      (node (ref "P2") (pin "16") (pinfunction "16_16") (pintype "passive"))
    )
    (net (code "115") (name "unconnected-(P2-Pad17)") (class "Default")
      (node (ref "P2") (pin "17") (pinfunction "17_17") (pintype "passive"))
    )
    (net (code "116") (name "unconnected-(P2-Pad18)") (class "Default")
      (node (ref "P2") (pin "18") (pinfunction "18_18") (pintype "passive"))
    )
    (net (code "117") (name "unconnected-(P2-Pad19)") (class "Default")
      (node (ref "P2") (pin "19") (pinfunction "19_19") (pintype "passive"))
    )
    (net (code "118") (name "unconnected-(P2-Pad20)") (class "Default")
      (node (ref "P2") (pin "20") (pinfunction "20_20") (pintype "passive"))
    )
    (net (code "119") (name "unconnected-(P2-Pad21)") (class "Default")
      (node (ref "P2") (pin "21") (pinfunction "21_21") (pintype "passive"))
    )
    (net (code "120") (name "unconnected-(P2-Pad23)") (class "Default")
      (node (ref "P2") (pin "23") (pinfunction "23_23") (pintype "passive"))
    )
    (net (code "121") (name "unconnected-(P2-Pad24)") (class "Default")
      (node (ref "P2") (pin "24") (pinfunction "24_24") (pintype "passive"))
    )
    (net (code "122") (name "unconnected-(P2-Pad26)") (class "Default")
      (node (ref "P2") (pin "26") (pinfunction "26_26") (pintype "passive"))
    )
    (net (code "123") (name "unconnected-(P2-Pad28)") (class "Default")
      (node (ref "P2") (pin "28") (pinfunction "28_28") (pintype "passive"))
    )
    (net (code "124") (name "unconnected-(P2-Pad29)") (class "Default")
      (node (ref "P2") (pin "29") (pinfunction "29_29") (pintype "passive"))
    )
    (net (code "125") (name "unconnected-(P3-Pad9)") (class "Default")
      (node (ref "P3") (pin "9") (pinfunction "9_9") (pintype "passive"))
    )
    (net (code "126") (name "unconnected-(P3-Pad10)") (class "Default")
      (node (ref "P3") (pin "10") (pinfunction "10_10") (pintype "passive"))
    )
    (net (code "127") (name "unconnected-(P3-Pad11)") (class "Default")
      (node (ref "P3") (pin "11") (pinfunction "11_11") (pintype "passive"))
    )
    (net (code "128") (name "unconnected-(P3-Pad12)") (class "Default")
      (node (ref "P3") (pin "12") (pinfunction "12_12") (pintype "passive"))
    )
    (net (code "129") (name "unconnected-(P3-Pad13)") (class "Default")
      (node (ref "P3") (pin "13") (pinfunction "13_13") (pintype "passive"))
    )
    (net (code "130") (name "unconnected-(P3-Pad14)") (class "Default")
      (node (ref "P3") (pin "14") (pinfunction "14_14") (pintype "passive"))
    )
    (net (code "131") (name "unconnected-(P3-Pad15)") (class "Default")
      (node (ref "P3") (pin "15") (pinfunction "15_15") (pintype "passive"))
    )
    (net (code "132") (name "unconnected-(P3-Pad16)") (class "Default")
      (node (ref "P3") (pin "16") (pinfunction "16_16") (pintype "passive"))
    )
    (net (code "133") (name "unconnected-(P3-Pad19)") (class "Default")
      (node (ref "P3") (pin "19") (pinfunction "19_19") (pintype "passive"))
    )
    (net (code "134") (name "unconnected-(P3-Pad20)") (class "Default")
      (node (ref "P3") (pin "20") (pinfunction "20_20") (pintype "passive"))
    )
    (net (code "135") (name "unconnected-(P3-Pad21)") (class "Default")
      (node (ref "P3") (pin "21") (pinfunction "21_21") (pintype "passive"))
    )
    (net (code "136") (name "unconnected-(P3-Pad22)") (class "Default")
      (node (ref "P3") (pin "22") (pinfunction "22_22") (pintype "passive"))
    )
    (net (code "137") (name "unconnected-(P3-Pad24)") (class "Default")
      (node (ref "P3") (pin "24") (pinfunction "24_24") (pintype "passive"))
    )
    (net (code "138") (name "unconnected-(P3-Pad28)") (class "Default")
      (node (ref "P3") (pin "28") (pinfunction "28_28") (pintype "passive"))
    )
    (net (code "139") (name "unconnected-(P3-Pad30)") (class "Default")
      (node (ref "P3") (pin "30") (pinfunction "30_30") (pintype "passive"))
    )
    (net (code "140") (name "unconnected-(P4-Pad1)") (class "Default")
      (node (ref "P4") (pin "1") (pinfunction "1_1") (pintype "passive"))
    )
    (net (code "141") (name "unconnected-(P4-Pad2)") (class "Default")
      (node (ref "P4") (pin "2") (pinfunction "2_2") (pintype "passive"))
    )
    (net (code "142") (name "unconnected-(P4-Pad3)") (class "Default")
      (node (ref "P4") (pin "3") (pinfunction "3_3") (pintype "passive"))
    )
    (net (code "143") (name "unconnected-(P4-Pad7)") (class "Default")
      (node (ref "P4") (pin "7") (pinfunction "7_7") (pintype "passive"))
    )
    (net (code "144") (name "unconnected-(P4-Pad8)") (class "Default")
      (node (ref "P4") (pin "8") (pinfunction "8_8") (pintype "passive"))
    )
    (net (code "145") (name "unconnected-(P4-Pad11)") (class "Default")
      (node (ref "P4") (pin "11") (pinfunction "11_11") (pintype "passive"))
    )
    (net (code "146") (name "unconnected-(P4-Pad12)") (class "Default")
      (node (ref "P4") (pin "12") (pinfunction "12_12") (pintype "passive"))
    )
    (net (code "147") (name "unconnected-(P4-Pad13)") (class "Default")
      (node (ref "P4") (pin "13") (pinfunction "13_13") (pintype "passive"))
    )
    (net (code "148") (name "unconnected-(P4-Pad14)") (class "Default")
      (node (ref "P4") (pin "14") (pinfunction "14_14") (pintype "passive"))
    )
    (net (code "149") (name "unconnected-(P4-Pad15)") (class "Default")
      (node (ref "P4") (pin "15") (pinfunction "15_15") (pintype "passive"))
    )
    (net (code "150") (name "unconnected-(P4-Pad16)") (class "Default")
      (node (ref "P4") (pin "16") (pinfunction "16_16") (pintype "passive"))
    )
    (net (code "151") (name "unconnected-(P4-Pad17)") (class "Default")
      (node (ref "P4") (pin "17") (pinfunction "17_17") (pintype "passive"))
    )
    (net (code "152") (name "unconnected-(P4-Pad19)") (class "Default")
      (node (ref "P4") (pin "19") (pinfunction "19_19") (pintype "passive"))
    )
    (net (code "153") (name "unconnected-(P4-Pad20)") (class "Default")
      (node (ref "P4") (pin "20") (pinfunction "20_20") (pintype "passive"))
    )
    (net (code "154") (name "unconnected-(P4-Pad22)") (class "Default")
      (node (ref "P4") (pin "22") (pinfunction "22_22") (pintype "passive"))
    )
    (net (code "155") (name "unconnected-(P4-Pad30)") (class "Default")
      (node (ref "P4") (pin "30") (pinfunction "30_30") (pintype "passive"))
    )
  )
)
